# LCD.net
KiCad netlist of a schematic drawn in Altium Designer
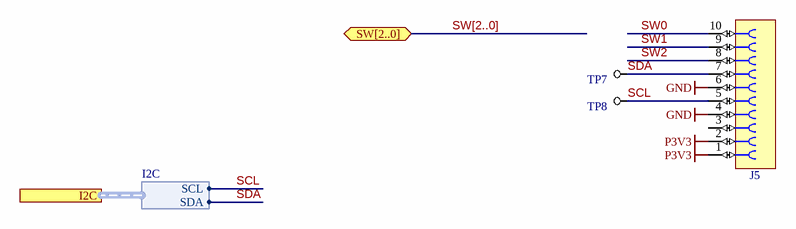
[diagram p0: LCD.SchDoc]

(export (version "E")
  (design (tool "Eeschema 10.0.6"))
  (components
    (comp (ref "J5")
      (value "FFC")
      (footprint "WURTH_686 110 144 22")
      (description "Connector 10 Female")
      (fields
        (field (name "PART NUMBER") "WURTH_686 110 144 22")
        (field (name "MANUFACTURER") "WURTH ELEKTRONIK")
        (field (name "AUTHOR") "CERN DEM JMW")
      )
      (libsource (lib "Connectors") (part "Connector 10 Female"))
    )
    (comp (ref "TP7")
      (value "TP")
      (footprint "TP")
      (description "Testpoint")
      (libsource (lib "LIBRARY_SCH") (part "TP"))
    )
    (comp (ref "TP8")
      (value "TP")
      (footprint "TP")
      (description "Testpoint")
      (libsource (lib "LIBRARY_SCH") (part "TP"))
    )
  )
  (nets
    (net (code "2") (name "/SCL") (class "Default")
      (node (ref "J5") (pin "5") (pinfunction "5_5") (pintype "bidirectional"))
      (node (ref "TP8") (pin "1") (pintype "passive"))
    )
    (net (code "3") (name "/SDA") (class "Default")
      (node (ref "J5") (pin "7") (pinfunction "7_7") (pintype "bidirectional"))
      (node (ref "TP7") (pin "1") (pintype "passive"))
    )
    (net (code "4") (name "/SW0") (class "Default")
      (node (ref "J5") (pin "10") (pinfunction "10_10") (pintype "bidirectional"))
    )
    (net (code "5") (name "/SW1") (class "Default")
      (node (ref "J5") (pin "9") (pinfunction "9_9") (pintype "bidirectional"))
    )
    (net (code "6") (name "/SW2") (class "Default")
      (node (ref "J5") (pin "8") (pinfunction "8_8") (pintype "bidirectional"))
    )
    (net (code "9") (name "GND") (class "Default")
      (node (ref "J5") (pin "4") (pinfunction "4_4") (pintype "bidirectional"))
      (node (ref "J5") (pin "6") (pinfunction "6_6") (pintype "bidirectional"))
    )
    (net (code "10") (name "P3V3") (class "Default")
      (node (ref "J5") (pin "1") (pinfunction "1_1") (pintype "bidirectional"))
      (node (ref "J5") (pin "2") (pinfunction "2_2") (pintype "bidirectional"))
    )
    (net (code "11") (name "unconnected-(J5-Pad3)") (class "Default")
      (node (ref "J5") (pin "3") (pinfunction "3_3") (pintype "bidirectional"))
    )
  )
)
